# EMMC_NANDFLASH_BGA153.net
KiCad netlist of a schematic drawn in Altium Designer
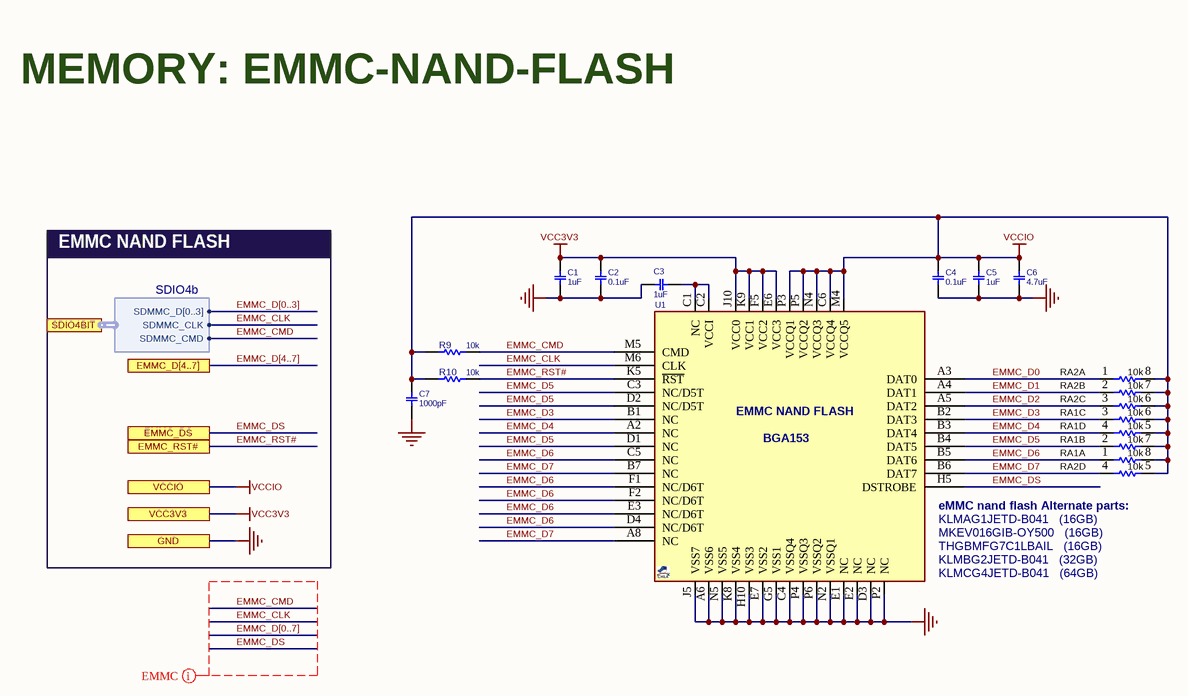
[diagram p0: EMMC_NANDFLASH_BGA153.SchDoc]

(export (version "E")
  (design (tool "Eeschema 10.0.6"))
  (components
    (comp (ref "C1")
      (value "1uF")
      (footprint "C0402")
      (description "CAP, MLCC")
      (fields (field (name "MANF_P#") "GMK105ABJ105KV-F") (field (name "MANF") "Taiyo Yuden"))
      (libsource (lib "passive_smd") (part "CAP_SMD_MLCC"))
    )
    (comp (ref "C2")
      (value "0.1uF")
      (footprint "C0402")
      (description "CAP, MLCC")
      (fields (field (name "MANF_P#") "GRM155R71H104KE14D") (field (name "MANF") "Murata"))
      (libsource (lib "passive_smd") (part "CAP_SMD_MLCC"))
    )
    (comp (ref "C3")
      (value "1uF")
      (footprint "C0402")
      (description "CAP, MLCC")
      (fields (field (name "MANF_P#") "GMK105ABJ105KV-F") (field (name "MANF") "Taiyo Yuden"))
      (libsource (lib "passive_smd") (part "CAP_SMD_MLCC"))
    )
    (comp (ref "C4")
      (value "0.1uF")
      (footprint "C0402")
      (description "CAP, MLCC")
      (fields (field (name "MANF_P#") "GRM155R71H104KE14D") (field (name "MANF") "Murata"))
      (libsource (lib "passive_smd") (part "CAP_SMD_MLCC"))
    )
    (comp (ref "C5")
      (value "1uF")
      (footprint "C0402")
      (description "CAP, MLCC")
      (fields (field (name "MANF_P#") "GMK105ABJ105KV-F") (field (name "MANF") "Taiyo Yuden"))
      (libsource (lib "passive_smd") (part "CAP_SMD_MLCC"))
    )
    (comp (ref "C6")
      (value "4.7uF")
      (footprint "C0402")
      (description "CAP, MLCC")
      (fields (field (name "MANF_P#") "LMK105BBJ475MVLF") (field (name "MANF") "Taiyo Yuden"))
      (libsource (lib "passive_smd") (part "CAP_SMD_MLCC"))
    )
    (comp (ref "C7")
      (value "1000pF")
      (footprint "C0402")
      (description "CAP, MLCC")
      (fields (field (name "MANF_P#") "CC0402JRNPO9BN102") (field (name "MANF") "Yageo"))
      (libsource (lib "mlcc_smd_passive") (part "CAP_SMD_MLCC"))
    )
    (comp (ref "R9")
      (value "10k")
      (footprint "R0402")
      (description "RESISTOR, SMD")
      (libsource (lib "passive_res_smd") (part "RES_SMD"))
    )
    (comp (ref "R10")
      (value "10k")
      (footprint "R0402")
      (description "RESISTOR, SMD")
      (libsource (lib "passive_res_smd") (part "RES_SMD"))
    )
    (comp (ref "RA1")
      (value "10k")
      (footprint "RP0402X4A")
      (description "RESISTOR, SMD, PACKX4")
      (fields (field (name "MANF") "MANF") (field (name "MANF_P#") "MANF_PART#"))
      (libsource (lib "passive_smd") (part "RES_SMD_PACK_X4"))
    )
    (comp (ref "RA2")
      (value "10k")
      (footprint "RP0402X4A")
      (description "RESISTOR, SMD, PACKX4")
      (fields (field (name "MANF") "MANF") (field (name "MANF_P#") "MANF_PART#"))
      (libsource (lib "passive_smd") (part "RES_SMD_PACK_X4"))
    )
    (comp (ref "U1")
      (value "eMMC_16GB")
      (footprint "BGA50_153_EMMC")
      (description "eMMC NAND FLASH, 16GB, 128Gb (16G x 8), 153-VFBGA")
      (fields (field (name "MANF_P#") "KLMAG2GEAC-B031") (field (name "MANF") "Samsung"))
      (libsource (lib "H6") (part "KLMAG2GEAC_16GB_BGA153"))
    )
  )
  (nets
    (net (code "2") (name "/EMMC_CLK") (class "Default")
      (node (ref "U1") (pin "M6") (pinfunction "CLK_M6") (pintype "passive"))
    )
    (net (code "3") (name "/EMMC_CMD") (class "Default")
      (node (ref "R9") (pin "1") (pinfunction "1_1") (pintype "passive"))
      (node (ref "U1") (pin "M5") (pinfunction "CMD_M5") (pintype "passive"))
    )
    (net (code "4") (name "/EMMC_D0") (class "Default")
      (node (ref "RA2") (pin "1") (pinfunction "1_1") (pintype "passive"))
      (node (ref "U1") (pin "A3") (pinfunction "DAT0_A3") (pintype "passive"))
    )
    (net (code "5") (name "/EMMC_D1") (class "Default")
      (node (ref "RA2") (pin "2") (pinfunction "2_2") (pintype "passive"))
      (node (ref "U1") (pin "A4") (pinfunction "DAT1_A4") (pintype "passive"))
    )
    (net (code "6") (name "/EMMC_D2") (class "Default")
      (node (ref "RA2") (pin "3") (pinfunction "3_3") (pintype "passive"))
      (node (ref "U1") (pin "A5") (pinfunction "DAT2_A5") (pintype "passive"))
    )
    (net (code "7") (name "/EMMC_D3") (class "Default")
      (node (ref "RA1") (pin "3") (pinfunction "3_3") (pintype "passive"))
      (node (ref "U1") (pin "B1") (pinfunction "NC_B1") (pintype "passive"))
      (node (ref "U1") (pin "B2") (pinfunction "DAT3_B2") (pintype "passive"))
    )
    (net (code "8") (name "/EMMC_D4") (class "Default")
      (node (ref "RA1") (pin "4") (pinfunction "4_4") (pintype "passive"))
      (node (ref "U1") (pin "A2") (pinfunction "NC_A2") (pintype "passive"))
      (node (ref "U1") (pin "B3") (pinfunction "DAT4_B3") (pintype "passive"))
    )
    (net (code "9") (name "/EMMC_D5") (class "Default")
      (node (ref "RA1") (pin "2") (pinfunction "2_2") (pintype "passive"))
      (node (ref "U1") (pin "B4") (pinfunction "DAT5_B4") (pintype "passive"))
      (node (ref "U1") (pin "C3") (pinfunction "NC/D5T_C3") (pintype "passive"))
      (node (ref "U1") (pin "D1") (pinfunction "NC_D1") (pintype "passive"))
      (node (ref "U1") (pin "D2") (pinfunction "NC/D5T_D2") (pintype "passive"))
    )
    (net (code "10") (name "/EMMC_D6") (class "Default")
      (node (ref "RA1") (pin "1") (pinfunction "1_1") (pintype "passive"))
      (node (ref "U1") (pin "B5") (pinfunction "DAT6_B5") (pintype "passive"))
      (node (ref "U1") (pin "C5") (pinfunction "NC_C5") (pintype "power_in"))
      (node (ref "U1") (pin "D4") (pinfunction "NC/D6T_D4") (pintype "power_in"))
      (node (ref "U1") (pin "E3") (pinfunction "NC/D6T_E3") (pintype "power_in"))
      (node (ref "U1") (pin "F1") (pinfunction "NC/D6T_F1") (pintype "power_in"))
      (node (ref "U1") (pin "F2") (pinfunction "NC/D6T_F2") (pintype "power_in"))
    )
    (net (code "11") (name "/EMMC_D7") (class "Default")
      (node (ref "RA2") (pin "4") (pinfunction "4_4") (pintype "passive"))
      (node (ref "U1") (pin "A8") (pinfunction "NC_A8") (pintype "passive"))
      (node (ref "U1") (pin "B6") (pinfunction "DAT7_B6") (pintype "passive"))
      (node (ref "U1") (pin "B7") (pinfunction "NC_B7") (pintype "passive"))
    )
    (net (code "12") (name "/EMMC_DS") (class "Default")
      (node (ref "U1") (pin "H5") (pinfunction "DSTROBE_H5") (pintype "passive"))
    )
    (net (code "16") (name "/EMMC_RST#") (class "Default")
      (node (ref "R10") (pin "1") (pinfunction "1_1") (pintype "passive"))
      (node (ref "U1") (pin "K5") (pinfunction "~{RST}_K5") (pintype "passive"))
    )
    (net (code "18") (name "GND") (class "Default")
      (node (ref "C1") (pin "1") (pinfunction "1_1") (pintype "passive"))
      (node (ref "C2") (pin "1") (pinfunction "1_1") (pintype "passive"))
      (node (ref "C3") (pin "1") (pinfunction "1_1") (pintype "passive"))
      (node (ref "C4") (pin "1") (pinfunction "1_1") (pintype "passive"))
      (node (ref "C5") (pin "1") (pinfunction "1_1") (pintype "passive"))
      (node (ref "C6") (pin "1") (pinfunction "1_1") (pintype "passive"))
      (node (ref "C7") (pin "1") (pinfunction "1_1") (pintype "passive"))
      (node (ref "U1") (pin "A6") (pinfunction "VSS6_A6") (pintype "power_in"))
      (node (ref "U1") (pin "C4") (pinfunction "VSSQ4_C4") (pintype "passive"))
      (node (ref "U1") (pin "D3") (pinfunction "NC_D3") (pintype "power_in"))
      (node (ref "U1") (pin "E1") (pinfunction "NC_E1") (pintype "power_in"))
      (node (ref "U1") (pin "E2") (pinfunction "NC_E2") (pintype "power_in"))
      (node (ref "U1") (pin "E7") (pinfunction "VSS2_E7") (pintype "power_in"))
      (node (ref "U1") (pin "G5") (pinfunction "VSS1_G5") (pintype "power_in"))
      (node (ref "U1") (pin "H10") (pinfunction "VSS3_H10") (pintype "power_in"))
      (node (ref "U1") (pin "J5") (pinfunction "VSS7_J5") (pintype "power_in"))
      (node (ref "U1") (pin "K8") (pinfunction "VSS4_K8") (pintype "power_in"))
      (node (ref "U1") (pin "N2") (pinfunction "VSSQ1_N2") (pintype "power_in"))
      (node (ref "U1") (pin "N5") (pinfunction "VSS5_N5") (pintype "power_in"))
      (node (ref "U1") (pin "P2") (pinfunction "NC_P2") (pintype "power_in"))
      (node (ref "U1") (pin "P4") (pinfunction "VSSQ3_P4") (pintype "power_in"))
      (node (ref "U1") (pin "P6") (pinfunction "VSSQ2_P6") (pintype "power_in"))
    )
    (net (code "19") (name "Net-(U1-VCCI)") (class "Default")
      (node (ref "C3") (pin "2") (pinfunction "2_2") (pintype "passive"))
      (node (ref "U1") (pin "C1") (pinfunction "NC_C1") (pintype "power_in"))
      (node (ref "U1") (pin "C2") (pinfunction "VCCI_C2") (pintype "power_in"))
    )
    (net (code "20") (name "VCC3V3") (class "Default")
      (node (ref "C1") (pin "2") (pinfunction "2_2") (pintype "passive"))
      (node (ref "C2") (pin "2") (pinfunction "2_2") (pintype "passive"))
      (node (ref "U1") (pin "E6") (pinfunction "VCC3_E6") (pintype "power_in"))
      (node (ref "U1") (pin "F5") (pinfunction "VCC2_F5") (pintype "power_in"))
      (node (ref "U1") (pin "J10") (pinfunction "VCC0_J10") (pintype "passive"))
      (node (ref "U1") (pin "K9") (pinfunction "VCC1_K9") (pintype "power_in"))
    )
    (net (code "21") (name "VCCIO") (class "Default")
      (node (ref "C4") (pin "2") (pinfunction "2_2") (pintype "passive"))
      (node (ref "C5") (pin "2") (pinfunction "2_2") (pintype "passive"))
      (node (ref "C6") (pin "2") (pinfunction "2_2") (pintype "passive"))
      (node (ref "C7") (pin "2") (pinfunction "2_2") (pintype "passive"))
      (node (ref "R10") (pin "2") (pinfunction "2_2") (pintype "passive"))
      (node (ref "R9") (pin "2") (pinfunction "2_2") (pintype "passive"))
      (node (ref "RA1") (pin "5") (pinfunction "5_5") (pintype "passive"))
      (node (ref "RA1") (pin "6") (pinfunction "6_6") (pintype "passive"))
      (node (ref "RA1") (pin "7") (pinfunction "7_7") (pintype "passive"))
      (node (ref "RA1") (pin "8") (pinfunction "8_8") (pintype "passive"))
      (node (ref "RA2") (pin "5") (pinfunction "5_5") (pintype "passive"))
      (node (ref "RA2") (pin "6") (pinfunction "6_6") (pintype "passive"))
      (node (ref "RA2") (pin "7") (pinfunction "7_7") (pintype "passive"))
      (node (ref "RA2") (pin "8") (pinfunction "8_8") (pintype "passive"))
      (node (ref "U1") (pin "C6") (pinfunction "VCCQ4_C6") (pintype "passive"))
      (node (ref "U1") (pin "M4") (pinfunction "VCCQ5_M4") (pintype "power_in"))
      (node (ref "U1") (pin "N4") (pinfunction "VCCQ3_N4") (pintype "power_in"))
      (node (ref "U1") (pin "P3") (pinfunction "VCCQ1_P3") (pintype "power_in"))
      (node (ref "U1") (pin "P5") (pinfunction "VCCQ2_P5") (pintype "power_in"))
    )
  )
)
